# DIO-SMA16-MEZZ.net
KiCad netlist of a schematic drawn in Altium Designer
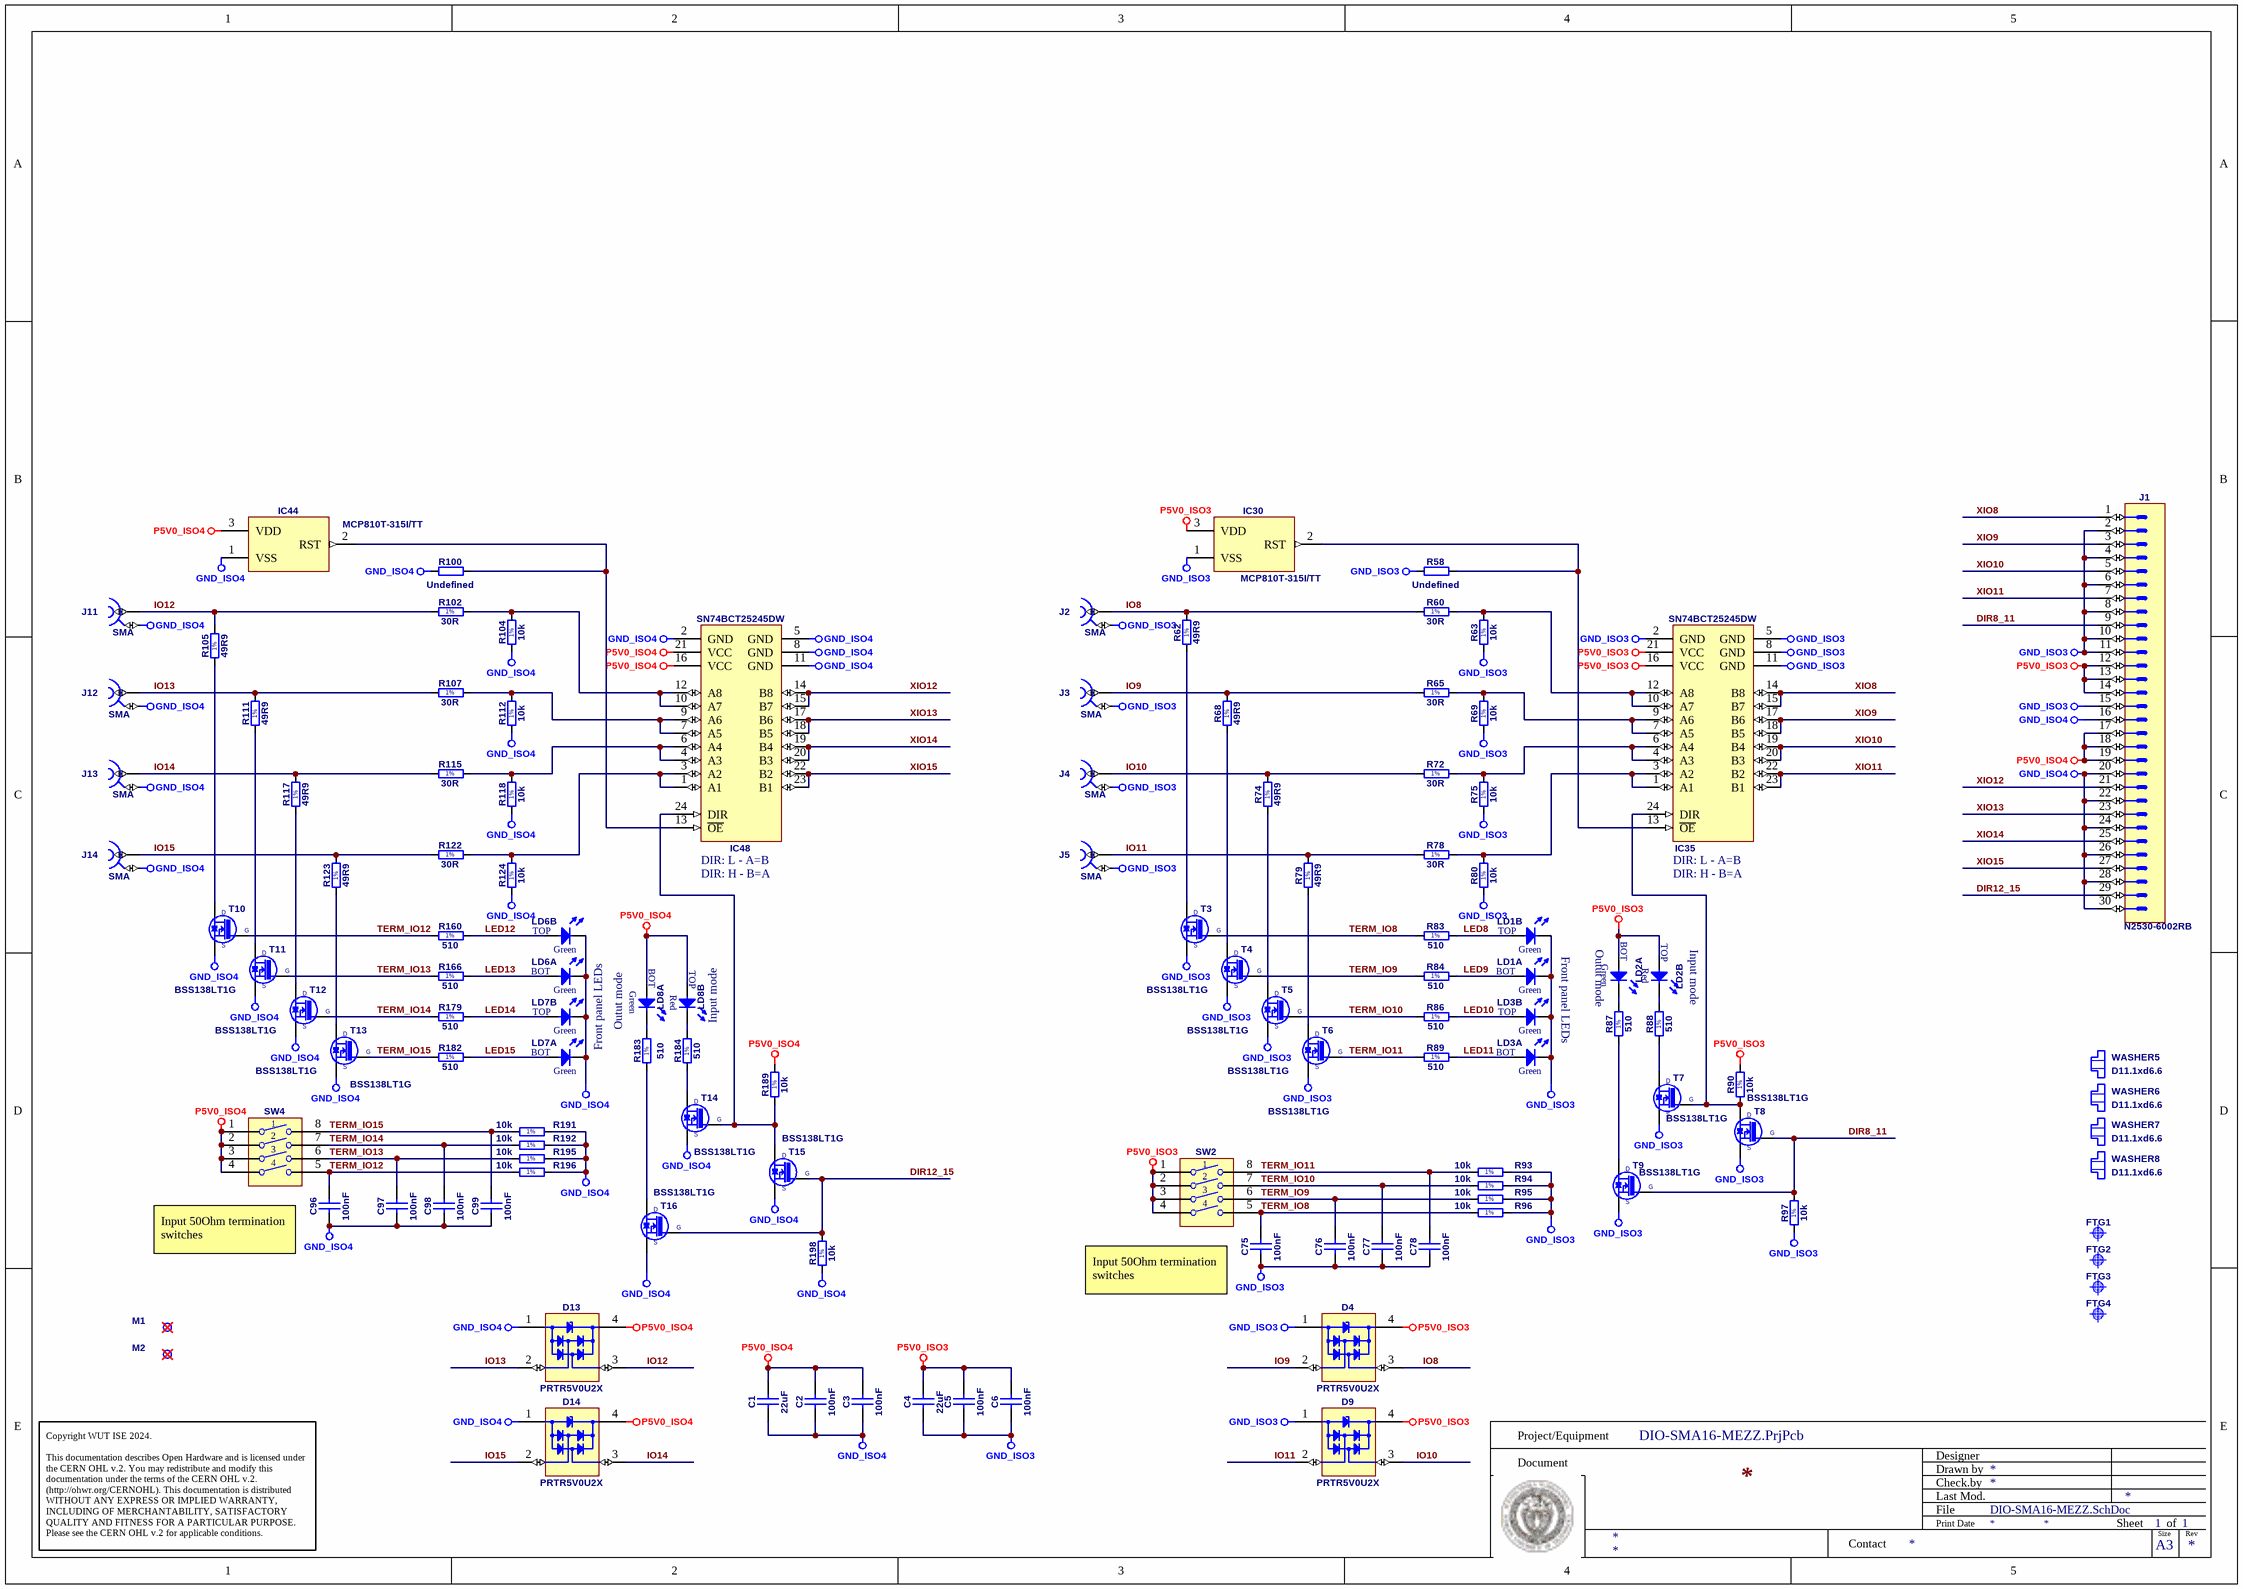
[diagram p0: DIO-SMA16-MEZZ.SchDoc]

(export (version "E")
  (design (tool "Eeschema 10.0.6"))
  (components
    (comp (ref "C1")
      (value "22uF")
      (footprint "CAPC2012X135N")
      (description "Non-polarised capacitor")
      (fields
        (field (name "PART NUMBER") "CC0805_22UF_16V_10%_X5R")
        (field (name "VOLTAGE") "16V")
        (field (name "AUTHOR") "CERN DEM JLC")
      )
      (libsource (lib "Capacitors") (part "Capacitor - non polarized"))
    )
    (comp (ref "C2")
      (value "100nF")
      (footprint "CAPC1005X55N")
      (description "Non-polarised capacitor")
      (fields
        (field (name "PART NUMBER") "CC0402_100NF_16V_10%_X5R")
        (field (name "VOLTAGE") "16V")
        (field (name "AUTHOR") "CERN DEM JLC")
      )
      (libsource (lib "Capacitors") (part "Capacitor - non polarized"))
    )
    (comp (ref "C3")
      (value "100nF")
      (footprint "CAPC1005X55N")
      (description "Non-polarised capacitor")
      (fields
        (field (name "PART NUMBER") "CC0402_100NF_16V_10%_X5R")
        (field (name "VOLTAGE") "16V")
        (field (name "AUTHOR") "CERN DEM JLC")
      )
      (libsource (lib "Capacitors") (part "Capacitor - non polarized"))
    )
    (comp (ref "C4")
      (value "22uF")
      (footprint "CAPC2012X135N")
      (description "Non-polarised capacitor")
      (fields
        (field (name "PART NUMBER") "CC0805_22UF_16V_10%_X5R")
        (field (name "VOLTAGE") "16V")
        (field (name "AUTHOR") "CERN DEM JLC")
      )
      (libsource (lib "Capacitors") (part "Capacitor - non polarized"))
    )
    (comp (ref "C5")
      (value "100nF")
      (footprint "CAPC1005X55N")
      (description "Non-polarised capacitor")
      (fields
        (field (name "PART NUMBER") "CC0402_100NF_16V_10%_X5R")
        (field (name "VOLTAGE") "16V")
        (field (name "AUTHOR") "CERN DEM JLC")
      )
      (libsource (lib "Capacitors") (part "Capacitor - non polarized"))
    )
    (comp (ref "C6")
      (value "100nF")
      (footprint "CAPC1005X55N")
      (description "Non-polarised capacitor")
      (fields
        (field (name "PART NUMBER") "CC0402_100NF_16V_10%_X5R")
        (field (name "VOLTAGE") "16V")
        (field (name "AUTHOR") "CERN DEM JLC")
      )
      (libsource (lib "Capacitors") (part "Capacitor - non polarized"))
    )
    (comp (ref "C75")
      (value "100nF")
      (footprint "CAPC1005X55N")
      (description "Non-polarised capacitor")
      (fields
        (field (name "PART NUMBER") "CC0402_100NF_16V_10%_X5R")
        (field (name "VOLTAGE") "16V")
        (field (name "AUTHOR") "CERN DEM JLC")
      )
      (libsource (lib "Capacitors") (part "Capacitor - non polarized"))
    )
    (comp (ref "C76")
      (value "100nF")
      (footprint "CAPC1005X55N")
      (description "Non-polarised capacitor")
      (fields
        (field (name "PART NUMBER") "CC0402_100NF_16V_10%_X5R")
        (field (name "VOLTAGE") "16V")
        (field (name "AUTHOR") "CERN DEM JLC")
      )
      (libsource (lib "Capacitors") (part "Capacitor - non polarized"))
    )
    (comp (ref "C77")
      (value "100nF")
      (footprint "CAPC1005X55N")
      (description "Non-polarised capacitor")
      (fields
        (field (name "PART NUMBER") "CC0402_100NF_16V_10%_X5R")
        (field (name "VOLTAGE") "16V")
        (field (name "AUTHOR") "CERN DEM JLC")
      )
      (libsource (lib "Capacitors") (part "Capacitor - non polarized"))
    )
    (comp (ref "C78")
      (value "100nF")
      (footprint "CAPC1005X55N")
      (description "Non-polarised capacitor")
      (fields
        (field (name "PART NUMBER") "CC0402_100NF_16V_10%_X5R")
        (field (name "VOLTAGE") "16V")
        (field (name "AUTHOR") "CERN DEM JLC")
      )
      (libsource (lib "Capacitors") (part "Capacitor - non polarized"))
    )
    (comp (ref "C96")
      (value "100nF")
      (footprint "CAPC1005X55N")
      (description "Non-polarised capacitor")
      (fields
        (field (name "PART NUMBER") "CC0402_100NF_16V_10%_X5R")
        (field (name "VOLTAGE") "16V")
        (field (name "AUTHOR") "CERN DEM JLC")
      )
      (libsource (lib "Capacitors") (part "Capacitor - non polarized"))
    )
    (comp (ref "C97")
      (value "100nF")
      (footprint "CAPC1005X55N")
      (description "Non-polarised capacitor")
      (fields
        (field (name "PART NUMBER") "CC0402_100NF_16V_10%_X5R")
        (field (name "VOLTAGE") "16V")
        (field (name "AUTHOR") "CERN DEM JLC")
      )
      (libsource (lib "Capacitors") (part "Capacitor - non polarized"))
    )
    (comp (ref "C98")
      (value "100nF")
      (footprint "CAPC1005X55N")
      (description "Non-polarised capacitor")
      (fields
        (field (name "PART NUMBER") "CC0402_100NF_16V_10%_X5R")
        (field (name "VOLTAGE") "16V")
        (field (name "AUTHOR") "CERN DEM JLC")
      )
      (libsource (lib "Capacitors") (part "Capacitor - non polarized"))
    )
    (comp (ref "C99")
      (value "100nF")
      (footprint "CAPC1005X55N")
      (description "Non-polarised capacitor")
      (fields
        (field (name "PART NUMBER") "CC0402_100NF_16V_10%_X5R")
        (field (name "VOLTAGE") "16V")
        (field (name "AUTHOR") "CERN DEM JLC")
      )
      (libsource (lib "Capacitors") (part "Capacitor - non polarized"))
    )
    (comp (ref "D4")
      (value "PRTR5V0U2X")
      (footprint "SOT190P230X110-4N")
      (description "Ultra Low Capacitance Double Rail-to-Rail ESD Protection Diode")
      (fields
        (field (name "VOLTAGE") "5.5V")
        (field (name "MANUFACTURER") "NXP SEMICONDUCTORS")
        (field (name "AUTHOR") "CERN DEM JLC")
      )
      (libsource (lib "ICs And Semiconductors") (part "PRTR5V0U2X"))
    )
    (comp (ref "D9")
      (value "PRTR5V0U2X")
      (footprint "SOT190P230X110-4N")
      (description "Ultra Low Capacitance Double Rail-to-Rail ESD Protection Diode")
      (fields
        (field (name "VOLTAGE") "5.5V")
        (field (name "MANUFACTURER") "NXP SEMICONDUCTORS")
        (field (name "AUTHOR") "CERN DEM JLC")
      )
      (libsource (lib "ICs And Semiconductors") (part "PRTR5V0U2X"))
    )
    (comp (ref "D13")
      (value "PRTR5V0U2X")
      (footprint "SOT190P230X110-4N")
      (description "Ultra Low Capacitance Double Rail-to-Rail ESD Protection Diode")
      (fields
        (field (name "VOLTAGE") "5.5V")
        (field (name "MANUFACTURER") "NXP SEMICONDUCTORS")
        (field (name "AUTHOR") "CERN DEM JLC")
      )
      (libsource (lib "ICs And Semiconductors") (part "PRTR5V0U2X"))
    )
    (comp (ref "D14")
      (value "PRTR5V0U2X")
      (footprint "SOT190P230X110-4N")
      (description "Ultra Low Capacitance Double Rail-to-Rail ESD Protection Diode")
      (fields
        (field (name "VOLTAGE") "5.5V")
        (field (name "MANUFACTURER") "NXP SEMICONDUCTORS")
        (field (name "AUTHOR") "CERN DEM JLC")
      )
      (libsource (lib "ICs And Semiconductors") (part "PRTR5V0U2X"))
    )
    (comp (ref "FTG1")
      (value "Use only in PCB")
      (footprint "FIDUCIAL_TOP_C100-200")
      (description "Fiducial Target")
      (fields (field (name "PART NUMBER") "FIDUCIAL_TARGET_C100-200") (field (name "AUTHOR") "CERN DEM JLC"))
      (libsource (lib "Eletro-mechanical") (part "Fiducial Target"))
    )
    (comp (ref "FTG2")
      (value "Use only in PCB")
      (footprint "FIDUCIAL_TOP_S100-200")
      (description "Fiducial Target")
      (fields (field (name "PART NUMBER") "FIDUCIAL_TARGET_S100-200") (field (name "AUTHOR") "CERN DEM JLC"))
      (libsource (lib "Eletro-mechanical") (part "Fiducial Target"))
    )
    (comp (ref "FTG3")
      (value "Use only in PCB")
      (footprint "FIDUCIAL_TOP_S100-200")
      (description "Fiducial Target")
      (fields (field (name "PART NUMBER") "FIDUCIAL_TARGET_S100-200") (field (name "AUTHOR") "CERN DEM JLC"))
      (libsource (lib "Eletro-mechanical") (part "Fiducial Target"))
    )
    (comp (ref "FTG4")
      (value "Use only in PCB")
      (footprint "FIDUCIAL_TOP_S100-200")
      (description "Fiducial Target")
      (fields (field (name "PART NUMBER") "FIDUCIAL_TARGET_S100-200") (field (name "AUTHOR") "CERN DEM JLC"))
      (libsource (lib "Eletro-mechanical") (part "Fiducial Target"))
    )
    (comp (ref "IC30")
      (value "MCP810T-315I/TT")
      (footprint "SOT95P237X112-3N")
      (description "3.075V Microcontroller Supervisory Circuit With Push-Pull Output")
      (fields (field (name "MANUFACTURER") "MICROCHIP TECHNOLOGY") (field (name "AUTHOR") "GK"))
      (libsource (lib "LIBRARY_SCH") (part "VMON_MCP810"))
    )
    (comp (ref "IC35")
      (value "SN74BCT25245DW")
      (footprint "SOIC127P1030X265-24N")
      (description "25 Ohms Octal Bus Transceiver With 3-State Outputs")
      (fields (field (name "MANUFACTURER") "TEXAS INSTRUMENTS") (field (name "AUTHOR") "CERN DEM JLC"))
      (libsource (lib "ICs And Semiconductors") (part "7425245"))
    )
    (comp (ref "IC44")
      (value "MCP810T-315I/TT")
      (footprint "SOT95P237X112-3N")
      (description "3.075V Microcontroller Supervisory Circuit With Push-Pull Output")
      (fields (field (name "MANUFACTURER") "MICROCHIP TECHNOLOGY") (field (name "AUTHOR") "GK"))
      (libsource (lib "LIBRARY_SCH") (part "VMON_MCP810"))
    )
    (comp (ref "IC48")
      (value "SN74BCT25245DW")
      (footprint "SOIC127P1030X265-24N")
      (description "25 Ohms Octal Bus Transceiver With 3-State Outputs")
      (fields (field (name "MANUFACTURER") "TEXAS INSTRUMENTS") (field (name "AUTHOR") "CERN DEM JLC"))
      (libsource (lib "ICs And Semiconductors") (part "7425245"))
    )
    (comp (ref "J1")
      (value "~")
      (footprint "3M_N2530-6002RB")
      (description "Connector 30 Male")
      (fields
        (field (name "PART NUMBER") "3M_N2530-6002RB")
        (field (name "MANUFACTURER") "3M")
        (field (name "MANUFACTURER PART NUMBER") "N2530-6002RB")
        (field (name "AUTHOR") "CERN DEM JLC")
      )
      (libsource (lib "Connectors") (part "Connector 30 Male"))
    )
    (comp (ref "J2")
      (value "SMA")
      (footprint "DELOCK_65848")
      (description "50 Ohm Through Hole SMA Right Angle PCB Jack")
      (fields
        (field (name "PART NUMBER") "DELOCK_65848")
        (field (name "MANUFACTURER") "DELOCK")
        (field (name "AUTHOR") "GK")
      )
      (libsource (lib "Connectors") (part "CON_SMA_DELOCK_65848"))
    )
    (comp (ref "J3")
      (value "SMA")
      (footprint "MOLEX_73251-2121")
      (fields
        (field (name "PART NUMBER") "MOLEX_73251-2121")
        (field (name "MANUFACTURER") "MOLEX")
        (field (name "MANUFACTURER PART NUMBER") "73251-2121")
        (field (name "AUTHOR") "CERN DEM JLC")
      )
      (libsource (lib "Connectors") (part "Coax_1Female_1Shield"))
    )
    (comp (ref "J4")
      (value "SMA")
      (footprint "DELOCK_65848")
      (description "50 Ohm Through Hole SMA Right Angle PCB Jack")
      (fields
        (field (name "PART NUMBER") "DELOCK_65848")
        (field (name "MANUFACTURER") "DELOCK")
        (field (name "AUTHOR") "GK")
      )
      (libsource (lib "Connectors") (part "CON_SMA_DELOCK_65848"))
    )
    (comp (ref "J5")
      (value "SMA")
      (footprint "MOLEX_73251-2121")
      (fields
        (field (name "PART NUMBER") "MOLEX_73251-2121")
        (field (name "MANUFACTURER") "MOLEX")
        (field (name "MANUFACTURER PART NUMBER") "73251-2121")
        (field (name "AUTHOR") "CERN DEM JLC")
      )
      (libsource (lib "Connectors") (part "Coax_1Female_1Shield"))
    )
    (comp (ref "J11")
      (value "SMA")
      (footprint "DELOCK_65848")
      (description "50 Ohm Through Hole SMA Right Angle PCB Jack")
      (fields
        (field (name "PART NUMBER") "DELOCK_65848")
        (field (name "MANUFACTURER") "DELOCK")
        (field (name "AUTHOR") "GK")
      )
      (libsource (lib "Connectors") (part "CON_SMA_DELOCK_65848"))
    )
    (comp (ref "J12")
      (value "SMA")
      (footprint "MOLEX_73251-2121")
      (fields
        (field (name "PART NUMBER") "MOLEX_73251-2121")
        (field (name "MANUFACTURER") "MOLEX")
        (field (name "MANUFACTURER PART NUMBER") "73251-2121")
        (field (name "AUTHOR") "CERN DEM JLC")
      )
      (libsource (lib "Connectors") (part "Coax_1Female_1Shield"))
    )
    (comp (ref "J13")
      (value "SMA")
      (footprint "DELOCK_65848")
      (description "50 Ohm Through Hole SMA Right Angle PCB Jack")
      (fields
        (field (name "PART NUMBER") "DELOCK_65848")
        (field (name "MANUFACTURER") "DELOCK")
        (field (name "AUTHOR") "GK")
      )
      (libsource (lib "Connectors") (part "CON_SMA_DELOCK_65848"))
    )
    (comp (ref "J14")
      (value "SMA")
      (footprint "MOLEX_73251-2121")
      (fields
        (field (name "PART NUMBER") "MOLEX_73251-2121")
        (field (name "MANUFACTURER") "MOLEX")
        (field (name "MANUFACTURER PART NUMBER") "73251-2121")
        (field (name "AUTHOR") "CERN DEM JLC")
      )
      (libsource (lib "Connectors") (part "Coax_1Female_1Shield"))
    )
    (comp (ref "LD1")
      (value "Green/Green")
      (footprint "LED_DIALIGHT_571-0122F")
      (description "LED x2 Green 1C2A-BOT_3C4A-TOP")
      (fields
        (field (name "PART NUMBER") "LED_DIALIGHT_571-0122F")
        (field (name "MANUFACTURER") "DIALIGHT")
        (field (name "AUTHOR") "CERN DEM JLC")
      )
      (libsource (lib "ICs And Semiconductors") (part "LED x2 Green 1C2A-BOT_3C4A-TOP"))
    )
    (comp (ref "LD2")
      (value "Red/Green")
      (footprint "LED_DIALIGHT_571-0112F")
      (description "2x LED  Botom Green, Top Red")
      (fields
        (field (name "PART NUMBER") "LED_DIALIGHT_571-0112F")
        (field (name "MANUFACTURER") "DIALIGHT")
        (field (name "AUTHOR") "CERN DEM JLC")
      )
      (libsource (lib "ICs And Semiconductors") (part "LED x2 G-1C2A-BOT_R-3C4A-TOP"))
    )
    (comp (ref "LD3")
      (value "Green/Green")
      (footprint "LED_DIALIGHT_571-0122F")
      (description "LED x2 Green 1C2A-BOT_3C4A-TOP")
      (fields
        (field (name "PART NUMBER") "LED_DIALIGHT_571-0122F")
        (field (name "MANUFACTURER") "DIALIGHT")
        (field (name "AUTHOR") "CERN DEM JLC")
      )
      (libsource (lib "ICs And Semiconductors") (part "LED x2 Green 1C2A-BOT_3C4A-TOP"))
    )
    (comp (ref "LD6")
      (value "Green/Green")
      (footprint "LED_DIALIGHT_571-0122F")
      (description "LED x2 Green 1C2A-BOT_3C4A-TOP")
      (fields
        (field (name "PART NUMBER") "LED_DIALIGHT_571-0122F")
        (field (name "MANUFACTURER") "DIALIGHT")
        (field (name "AUTHOR") "CERN DEM JLC")
      )
      (libsource (lib "ICs And Semiconductors") (part "LED x2 Green 1C2A-BOT_3C4A-TOP"))
    )
    (comp (ref "LD7")
      (value "Green/Green")
      (footprint "LED_DIALIGHT_571-0122F")
      (description "LED x2 Green 1C2A-BOT_3C4A-TOP")
      (fields
        (field (name "PART NUMBER") "LED_DIALIGHT_571-0122F")
        (field (name "MANUFACTURER") "DIALIGHT")
        (field (name "AUTHOR") "CERN DEM JLC")
      )
      (libsource (lib "ICs And Semiconductors") (part "LED x2 Green 1C2A-BOT_3C4A-TOP"))
    )
    (comp (ref "LD8")
      (value "Red/Green")
      (footprint "LED_DIALIGHT_571-0112F")
      (description "2x LED  Botom Green, Top Red")
      (fields
        (field (name "PART NUMBER") "LED_DIALIGHT_571-0112F")
        (field (name "MANUFACTURER") "DIALIGHT")
        (field (name "AUTHOR") "CERN DEM JLC")
      )
      (libsource (lib "ICs And Semiconductors") (part "LED x2 G-1C2A-BOT_R-3C4A-TOP"))
    )
    (comp (ref "M1")
      (value "Plated Hole")
      (footprint "MTG300_600")
      (description "Single Terminal Socket")
      (fields (field (name "PART NUMBER") "PLATED_HOLE3.0_PAD6.0") (field (name "AUTHOR") "CERN DEM JLC"))
      (libsource (lib "Eletro-mechanical") (part "Single Terminal Socket"))
    )
    (comp (ref "M2")
      (value "Plated Hole")
      (footprint "MTG300_600")
      (description "Single Terminal Socket")
      (fields (field (name "PART NUMBER") "PLATED_HOLE3.0_PAD6.0") (field (name "AUTHOR") "CERN DEM JLC"))
      (libsource (lib "Eletro-mechanical") (part "Single Terminal Socket"))
    )
    (comp (ref "R58")
      (value "Undefined")
      (footprint "RESC1005X40N")
      (description "Resistor")
      (fields (field (name "PART NUMBER") "R0402_NO-VALUE") (field (name "AUTHOR") "CERN DEM JLC"))
      (libsource (lib "Resistors") (part "Resistor"))
    )
    (comp (ref "R60")
      (value "30R")
      (footprint "RESC3225X70N")
      (description "Resistor - 5%")
      (fields
        (field (name "PART NUMBER") "R1210_30R_5%_0.5W_200ppm")
        (field (name "POWER") "0.5W")
        (field (name "AUTHOR") "CERN DEM JMW")
      )
      (libsource (lib "LIBRARY_SCH") (part "R1210_30R_5%_0.5W_200PPM"))
    )
    (comp (ref "R62")
      (value "49R9")
      (footprint "RESC3225X70N")
      (description "Resistor - 1%")
      (fields
        (field (name "PART NUMBER") "R1210_49R9_1%_0.5W_100PPM_VISHAY_CRCW")
        (field (name "POWER") "0.5W")
        (field (name "AUTHOR") "CERN DEM JMW")
      )
      (libsource (lib "Resistors") (part "Resistor - 1%"))
    )
    (comp (ref "R63")
      (value "10k")
      (footprint "RESC1005X40N")
      (description "Resistor - 1%")
      (fields
        (field (name "PART NUMBER") "R0402_10K_1%_0.0625W_100PPM")
        (field (name "POWER") "0.0625W")
        (field (name "AUTHOR") "CERN DEM JLC")
      )
      (libsource (lib "Resistors") (part "Resistor - 1%"))
    )
    (comp (ref "R65")
      (value "30R")
      (footprint "RESC3225X70N")
      (description "Resistor - 5%")
      (fields
        (field (name "PART NUMBER") "R1210_30R_5%_0.5W_200ppm")
        (field (name "POWER") "0.5W")
        (field (name "AUTHOR") "CERN DEM JMW")
      )
      (libsource (lib "LIBRARY_SCH") (part "R1210_30R_5%_0.5W_200PPM"))
    )
    (comp (ref "R68")
      (value "49R9")
      (footprint "RESC3225X70N")
      (description "Resistor - 1%")
      (fields
        (field (name "PART NUMBER") "R1210_49R9_1%_0.5W_100PPM_VISHAY_CRCW")
        (field (name "POWER") "0.5W")
        (field (name "AUTHOR") "CERN DEM JMW")
      )
      (libsource (lib "Resistors") (part "Resistor - 1%"))
    )
    (comp (ref "R69")
      (value "10k")
      (footprint "RESC1005X40N")
      (description "Resistor - 1%")
      (fields
        (field (name "PART NUMBER") "R0402_10K_1%_0.0625W_100PPM")
        (field (name "POWER") "0.0625W")
        (field (name "AUTHOR") "CERN DEM JLC")
      )
      (libsource (lib "Resistors") (part "Resistor - 1%"))
    )
    (comp (ref "R72")
      (value "30R")
      (footprint "RESC3225X70N")
      (description "Resistor - 5%")
      (fields
        (field (name "PART NUMBER") "R1210_30R_5%_0.5W_200ppm")
        (field (name "POWER") "0.5W")
        (field (name "AUTHOR") "CERN DEM JMW")
      )
      (libsource (lib "LIBRARY_SCH") (part "R1210_30R_5%_0.5W_200PPM"))
    )
    (comp (ref "R74")
      (value "49R9")
      (footprint "RESC3225X70N")
      (description "Resistor - 1%")
      (fields
        (field (name "PART NUMBER") "R1210_49R9_1%_0.5W_100PPM_VISHAY_CRCW")
        (field (name "POWER") "0.5W")
        (field (name "AUTHOR") "CERN DEM JMW")
      )
      (libsource (lib "Resistors") (part "Resistor - 1%"))
    )
    (comp (ref "R75")
      (value "10k")
      (footprint "RESC1005X40N")
      (description "Resistor - 1%")
      (fields
        (field (name "PART NUMBER") "R0402_10K_1%_0.0625W_100PPM")
        (field (name "POWER") "0.0625W")
        (field (name "AUTHOR") "CERN DEM JLC")
      )
      (libsource (lib "Resistors") (part "Resistor - 1%"))
    )
    (comp (ref "R78")
      (value "30R")
      (footprint "RESC3225X70N")
      (description "Resistor - 5%")
      (fields
        (field (name "PART NUMBER") "R1210_30R_5%_0.5W_200ppm")
        (field (name "POWER") "0.5W")
        (field (name "AUTHOR") "CERN DEM JMW")
      )
      (libsource (lib "LIBRARY_SCH") (part "R1210_30R_5%_0.5W_200PPM"))
    )
    (comp (ref "R79")
      (value "49R9")
      (footprint "RESC3225X70N")
      (description "Resistor - 1%")
      (fields
        (field (name "PART NUMBER") "R1210_49R9_1%_0.5W_100PPM_VISHAY_CRCW")
        (field (name "POWER") "0.5W")
        (field (name "AUTHOR") "CERN DEM JMW")
      )
      (libsource (lib "Resistors") (part "Resistor - 1%"))
    )
    (comp (ref "R80")
      (value "10k")
      (footprint "RESC1005X40N")
      (description "Resistor - 1%")
      (fields
        (field (name "PART NUMBER") "R0402_10K_1%_0.0625W_100PPM")
        (field (name "POWER") "0.0625W")
        (field (name "AUTHOR") "CERN DEM JLC")
      )
      (libsource (lib "Resistors") (part "Resistor - 1%"))
    )
    (comp (ref "R83")
      (value "510")
      (footprint "RESC1005X40N")
      (description "Resistor - 1%")
      (fields
        (field (name "PART NUMBER") "R0402_510R_1%_0.0625W_100PPM")
        (field (name "POWER") "0.0625W")
        (field (name "AUTHOR") "CERN DEM JLC")
      )
      (libsource (lib "Resistors") (part "Resistor - 1%"))
    )
    (comp (ref "R84")
      (value "510")
      (footprint "RESC1005X40N")
      (description "Resistor - 1%")
      (fields
        (field (name "PART NUMBER") "R0402_510R_1%_0.0625W_100PPM")
        (field (name "POWER") "0.0625W")
        (field (name "AUTHOR") "CERN DEM JLC")
      )
      (libsource (lib "Resistors") (part "Resistor - 1%"))
    )
    (comp (ref "R86")
      (value "510")
      (footprint "RESC1005X40N")
      (description "Resistor - 1%")
      (fields
        (field (name "PART NUMBER") "R0402_510R_1%_0.0625W_100PPM")
        (field (name "POWER") "0.0625W")
        (field (name "AUTHOR") "CERN DEM JLC")
      )
      (libsource (lib "Resistors") (part "Resistor - 1%"))
    )
    (comp (ref "R87")
      (value "510")
      (footprint "RESC1005X40N")
      (description "Resistor - 1%")
      (fields
        (field (name "PART NUMBER") "R0402_510R_1%_0.0625W_100PPM")
        (field (name "POWER") "0.0625W")
        (field (name "AUTHOR") "CERN DEM JLC")
      )
      (libsource (lib "Resistors") (part "Resistor - 1%"))
    )
    (comp (ref "R88")
      (value "510")
      (footprint "RESC1005X40N")
      (description "Resistor - 1%")
      (fields
        (field (name "PART NUMBER") "R0402_510R_1%_0.0625W_100PPM")
        (field (name "POWER") "0.0625W")
        (field (name "AUTHOR") "CERN DEM JLC")
      )
      (libsource (lib "Resistors") (part "Resistor - 1%"))
    )
    (comp (ref "R89")
      (value "510")
      (footprint "RESC1005X40N")
      (description "Resistor - 1%")
      (fields
        (field (name "PART NUMBER") "R0402_510R_1%_0.0625W_100PPM")
        (field (name "POWER") "0.0625W")
        (field (name "AUTHOR") "CERN DEM JLC")
      )
      (libsource (lib "Resistors") (part "Resistor - 1%"))
    )
    (comp (ref "R90")
      (value "10k")
      (footprint "RESC1005X40N")
      (description "Resistor - 1%")
      (fields
        (field (name "PART NUMBER") "R0402_10K_1%_0.0625W_100PPM")
        (field (name "POWER") "0.0625W")
        (field (name "AUTHOR") "CERN DEM JLC")
      )
      (libsource (lib "Resistors") (part "Resistor - 1%"))
    )
    (comp (ref "R93")
      (value "10k")
      (footprint "RESC1005X40N")
      (description "Resistor - 1%")
      (fields
        (field (name "PART NUMBER") "R0402_10K_1%_0.0625W_100PPM")
        (field (name "POWER") "0.0625W")
        (field (name "AUTHOR") "CERN DEM JLC")
      )
      (libsource (lib "Resistors") (part "Resistor - 1%"))
    )
    (comp (ref "R94")
      (value "10k")
      (footprint "RESC1005X40N")
      (description "Resistor - 1%")
      (fields
        (field (name "PART NUMBER") "R0402_10K_1%_0.0625W_100PPM")
        (field (name "POWER") "0.0625W")
        (field (name "AUTHOR") "CERN DEM JLC")
      )
      (libsource (lib "Resistors") (part "Resistor - 1%"))
    )
    (comp (ref "R95")
      (value "10k")
      (footprint "RESC1005X40N")
      (description "Resistor - 1%")
      (fields
        (field (name "PART NUMBER") "R0402_10K_1%_0.0625W_100PPM")
        (field (name "POWER") "0.0625W")
        (field (name "AUTHOR") "CERN DEM JLC")
      )
      (libsource (lib "Resistors") (part "Resistor - 1%"))
    )
    (comp (ref "R96")
      (value "10k")
      (footprint "RESC1005X40N")
      (description "Resistor - 1%")
      (fields
        (field (name "PART NUMBER") "R0402_10K_1%_0.0625W_100PPM")
        (field (name "POWER") "0.0625W")
        (field (name "AUTHOR") "CERN DEM JLC")
      )
      (libsource (lib "Resistors") (part "Resistor - 1%"))
    )
    (comp (ref "R97")
      (value "10k")
      (footprint "RESC1005X40N")
      (description "Resistor - 1%")
      (fields
        (field (name "PART NUMBER") "R0402_10K_1%_0.0625W_100PPM")
        (field (name "POWER") "0.0625W")
        (field (name "AUTHOR") "CERN DEM JLC")
      )
      (libsource (lib "Resistors") (part "Resistor - 1%"))
    )
    (comp (ref "R100")
      (value "Undefined")
      (footprint "RESC1005X40N")
      (description "Resistor")
      (fields (field (name "PART NUMBER") "R0402_NO-VALUE") (field (name "AUTHOR") "CERN DEM JLC"))
      (libsource (lib "Resistors") (part "Resistor"))
    )
    (comp (ref "R102")
      (value "30R")
      (footprint "RESC3225X70N")
      (description "Resistor - 5%")
      (fields
        (field (name "PART NUMBER") "R1210_30R_5%_0.5W_200ppm")
        (field (name "POWER") "0.5W")
        (field (name "AUTHOR") "CERN DEM JMW")
      )
      (libsource (lib "LIBRARY_SCH") (part "R1210_30R_5%_0.5W_200PPM"))
    )
    (comp (ref "R104")
      (value "10k")
      (footprint "RESC1005X40N")
      (description "Resistor - 1%")
      (fields
        (field (name "PART NUMBER") "R0402_10K_1%_0.0625W_100PPM")
        (field (name "POWER") "0.0625W")
        (field (name "AUTHOR") "CERN DEM JLC")
      )
      (libsource (lib "Resistors") (part "Resistor - 1%"))
    )
    (comp (ref "R105")
      (value "49R9")
      (footprint "RESC3225X70N")
      (description "Resistor - 1%")
      (fields
        (field (name "PART NUMBER") "R1210_49R9_1%_0.5W_100PPM_VISHAY_CRCW")
        (field (name "POWER") "0.5W")
        (field (name "AUTHOR") "CERN DEM JMW")
      )
      (libsource (lib "Resistors") (part "Resistor - 1%"))
    )
    (comp (ref "R107")
      (value "30R")
      (footprint "RESC3225X70N")
      (description "Resistor - 5%")
      (fields
        (field (name "PART NUMBER") "R1210_30R_5%_0.5W_200ppm")
        (field (name "POWER") "0.5W")
        (field (name "AUTHOR") "CERN DEM JMW")
      )
      (libsource (lib "LIBRARY_SCH") (part "R1210_30R_5%_0.5W_200PPM"))
    )
    (comp (ref "R111")
      (value "49R9")
      (footprint "RESC3225X70N")
      (description "Resistor - 1%")
      (fields
        (field (name "PART NUMBER") "R1210_49R9_1%_0.5W_100PPM_VISHAY_CRCW")
        (field (name "POWER") "0.5W")
        (field (name "AUTHOR") "CERN DEM JMW")
      )
      (libsource (lib "Resistors") (part "Resistor - 1%"))
    )
    (comp (ref "R112")
      (value "10k")
      (footprint "RESC1005X40N")
      (description "Resistor - 1%")
      (fields
        (field (name "PART NUMBER") "R0402_10K_1%_0.0625W_100PPM")
        (field (name "POWER") "0.0625W")
        (field (name "AUTHOR") "CERN DEM JLC")
      )
      (libsource (lib "Resistors") (part "Resistor - 1%"))
    )
    (comp (ref "R115")
      (value "30R")
      (footprint "RESC3225X70N")
      (description "Resistor - 5%")
      (fields
        (field (name "PART NUMBER") "R1210_30R_5%_0.5W_200ppm")
        (field (name "POWER") "0.5W")
        (field (name "AUTHOR") "CERN DEM JMW")
      )
      (libsource (lib "LIBRARY_SCH") (part "R1210_30R_5%_0.5W_200PPM"))
    )
    (comp (ref "R117")
      (value "49R9")
      (footprint "RESC3225X70N")
      (description "Resistor - 1%")
      (fields
        (field (name "PART NUMBER") "R1210_49R9_1%_0.5W_100PPM_VISHAY_CRCW")
        (field (name "POWER") "0.5W")
        (field (name "AUTHOR") "CERN DEM JMW")
      )
      (libsource (lib "Resistors") (part "Resistor - 1%"))
    )
    (comp (ref "R118")
      (value "10k")
      (footprint "RESC1005X40N")
      (description "Resistor - 1%")
      (fields
        (field (name "PART NUMBER") "R0402_10K_1%_0.0625W_100PPM")
        (field (name "POWER") "0.0625W")
        (field (name "AUTHOR") "CERN DEM JLC")
      )
      (libsource (lib "Resistors") (part "Resistor - 1%"))
    )
    (comp (ref "R122")
      (value "30R")
      (footprint "RESC3225X70N")
      (description "Resistor - 5%")
      (fields
        (field (name "PART NUMBER") "R1210_30R_5%_0.5W_200ppm")
        (field (name "POWER") "0.5W")
        (field (name "AUTHOR") "CERN DEM JMW")
      )
      (libsource (lib "LIBRARY_SCH") (part "R1210_30R_5%_0.5W_200PPM"))
    )
    (comp (ref "R123")
      (value "49R9")
      (footprint "RESC3225X70N")
      (description "Resistor - 1%")
      (fields
        (field (name "PART NUMBER") "R1210_49R9_1%_0.5W_100PPM_VISHAY_CRCW")
        (field (name "POWER") "0.5W")
        (field (name "AUTHOR") "CERN DEM JMW")
      )
      (libsource (lib "Resistors") (part "Resistor - 1%"))
    )
    (comp (ref "R124")
      (value "10k")
      (footprint "RESC1005X40N")
      (description "Resistor - 1%")
      (fields
        (field (name "PART NUMBER") "R0402_10K_1%_0.0625W_100PPM")
        (field (name "POWER") "0.0625W")
        (field (name "AUTHOR") "CERN DEM JLC")
      )
      (libsource (lib "Resistors") (part "Resistor - 1%"))
    )
    (comp (ref "R160")
      (value "510")
      (footprint "RESC1005X40N")
      (description "Resistor - 1%")
      (fields
        (field (name "PART NUMBER") "R0402_510R_1%_0.0625W_100PPM")
        (field (name "POWER") "0.0625W")
        (field (name "AUTHOR") "CERN DEM JLC")
      )
      (libsource (lib "Resistors") (part "Resistor - 1%"))
    )
    (comp (ref "R166")
      (value "510")
      (footprint "RESC1005X40N")
      (description "Resistor - 1%")
      (fields
        (field (name "PART NUMBER") "R0402_510R_1%_0.0625W_100PPM")
        (field (name "POWER") "0.0625W")
        (field (name "AUTHOR") "CERN DEM JLC")
      )
      (libsource (lib "Resistors") (part "Resistor - 1%"))
    )
    (comp (ref "R179")
      (value "510")
      (footprint "RESC1005X40N")
      (description "Resistor - 1%")
      (fields
        (field (name "PART NUMBER") "R0402_510R_1%_0.0625W_100PPM")
        (field (name "POWER") "0.0625W")
        (field (name "AUTHOR") "CERN DEM JLC")
      )
      (libsource (lib "Resistors") (part "Resistor - 1%"))
    )
    (comp (ref "R182")
      (value "510")
      (footprint "RESC1005X40N")
      (description "Resistor - 1%")
      (fields
        (field (name "PART NUMBER") "R0402_510R_1%_0.0625W_100PPM")
        (field (name "POWER") "0.0625W")
        (field (name "AUTHOR") "CERN DEM JLC")
      )
      (libsource (lib "Resistors") (part "Resistor - 1%"))
    )
    (comp (ref "R183")
      (value "510")
      (footprint "RESC1005X40N")
      (description "Resistor - 1%")
      (fields
        (field (name "PART NUMBER") "R0402_510R_1%_0.0625W_100PPM")
        (field (name "POWER") "0.0625W")
        (field (name "AUTHOR") "CERN DEM JLC")
      )
      (libsource (lib "Resistors") (part "Resistor - 1%"))
    )
    (comp (ref "R184")
      (value "510")
      (footprint "RESC1005X40N")
      (description "Resistor - 1%")
      (fields
        (field (name "PART NUMBER") "R0402_510R_1%_0.0625W_100PPM")
        (field (name "POWER") "0.0625W")
        (field (name "AUTHOR") "CERN DEM JLC")
      )
      (libsource (lib "Resistors") (part "Resistor - 1%"))
    )
    (comp (ref "R189")
      (value "10k")
      (footprint "RESC1005X40N")
      (description "Resistor - 1%")
      (fields
        (field (name "PART NUMBER") "R0402_10K_1%_0.0625W_100PPM")
        (field (name "POWER") "0.0625W")
        (field (name "AUTHOR") "CERN DEM JLC")
      )
      (libsource (lib "Resistors") (part "Resistor - 1%"))
    )
    (comp (ref "R191")
      (value "10k")
      (footprint "RESC1005X40N")
      (description "Resistor - 1%")
      (fields
        (field (name "PART NUMBER") "R0402_10K_1%_0.0625W_100PPM")
        (field (name "POWER") "0.0625W")
        (field (name "AUTHOR") "CERN DEM JLC")
      )
      (libsource (lib "Resistors") (part "Resistor - 1%"))
    )
    (comp (ref "R192")
      (value "10k")
      (footprint "RESC1005X40N")
      (description "Resistor - 1%")
      (fields
        (field (name "PART NUMBER") "R0402_10K_1%_0.0625W_100PPM")
        (field (name "POWER") "0.0625W")
        (field (name "AUTHOR") "CERN DEM JLC")
      )
      (libsource (lib "Resistors") (part "Resistor - 1%"))
    )
    (comp (ref "R195")
      (value "10k")
      (footprint "RESC1005X40N")
      (description "Resistor - 1%")
      (fields
        (field (name "PART NUMBER") "R0402_10K_1%_0.0625W_100PPM")
        (field (name "POWER") "0.0625W")
        (field (name "AUTHOR") "CERN DEM JLC")
      )
      (libsource (lib "Resistors") (part "Resistor - 1%"))
    )
    (comp (ref "R196")
      (value "10k")
      (footprint "RESC1005X40N")
      (description "Resistor - 1%")
      (fields
        (field (name "PART NUMBER") "R0402_10K_1%_0.0625W_100PPM")
        (field (name "POWER") "0.0625W")
        (field (name "AUTHOR") "CERN DEM JLC")
      )
      (libsource (lib "Resistors") (part "Resistor - 1%"))
    )
    (comp (ref "R198")
      (value "10k")
      (footprint "RESC1005X40N")
      (description "Resistor - 1%")
      (fields
        (field (name "PART NUMBER") "R0402_10K_1%_0.0625W_100PPM")
        (field (name "POWER") "0.0625W")
        (field (name "AUTHOR") "CERN DEM JLC")
      )
      (libsource (lib "Resistors") (part "Resistor - 1%"))
    )
    (comp (ref "SW2")
      (value "Switch")
      (footprint "SW_OMRON_A6S-4102-H")
      (description "4 Ways SPST DIP Switch")
      (fields
        (field (name "PART NUMBER") "SW_OMRON_A6S-4102-H")
        (field (name "MANUFACTURER") "OMRON")
        (field (name "AUTHOR") "CERN DEM JMW")
      )
      (libsource (lib "Eletro-mechanical") (part "SW 4x SPST DIP Switch"))
    )
    (comp (ref "SW4")
      (value "Switch")
      (footprint "SW_OMRON_A6S-4102-H")
      (description "4 Ways SPST DIP Switch")
      (fields
        (field (name "PART NUMBER") "SW_OMRON_A6S-4102-H")
        (field (name "MANUFACTURER") "OMRON")
        (field (name "AUTHOR") "CERN DEM JMW")
      )
      (libsource (lib "Eletro-mechanical") (part "SW 4x SPST DIP Switch"))
    )
    (comp (ref "T3")
      (value "BSS138LT1G")
      (footprint "SOT95P240X110-3N")
      (description "N-CHANNEL MOSFET WITH DIODE")
      (fields (field (name "MANUFACTURER") "ON SEMICONDUCTOR") (field (name "AUTHOR") "CERN DEM JLC"))
      (libsource (lib "ICs And Semiconductors") (part "N-MOSFET-D 1G 2S 3D"))
    )
    (comp (ref "T4")
      (value "BSS138LT1G")
      (footprint "SOT95P240X110-3N")
      (description "N-CHANNEL MOSFET WITH DIODE")
      (fields (field (name "MANUFACTURER") "ON SEMICONDUCTOR") (field (name "AUTHOR") "CERN DEM JLC"))
      (libsource (lib "ICs And Semiconductors") (part "N-MOSFET-D 1G 2S 3D"))
    )
    (comp (ref "T5")
      (value "BSS138LT1G")
      (footprint "SOT95P240X110-3N")
      (description "N-CHANNEL MOSFET WITH DIODE")
      (fields (field (name "MANUFACTURER") "ON SEMICONDUCTOR") (field (name "AUTHOR") "CERN DEM JLC"))
      (libsource (lib "ICs And Semiconductors") (part "N-MOSFET-D 1G 2S 3D"))
    )
    (comp (ref "T6")
      (value "BSS138LT1G")
      (footprint "SOT95P240X110-3N")
      (description "N-CHANNEL MOSFET WITH DIODE")
      (fields (field (name "MANUFACTURER") "ON SEMICONDUCTOR") (field (name "AUTHOR") "CERN DEM JLC"))
      (libsource (lib "ICs And Semiconductors") (part "N-MOSFET-D 1G 2S 3D"))
    )
    (comp (ref "T7")
      (value "BSS138LT1G")
      (footprint "SOT95P240X110-3N")
      (description "N-CHANNEL MOSFET WITH DIODE")
      (fields (field (name "MANUFACTURER") "ON SEMICONDUCTOR") (field (name "AUTHOR") "CERN DEM JLC"))
      (libsource (lib "ICs And Semiconductors") (part "N-MOSFET-D 1G 2S 3D"))
    )
    (comp (ref "T8")
      (value "BSS138LT1G")
      (footprint "SOT95P240X110-3N")
      (description "N-CHANNEL MOSFET WITH DIODE")
      (fields (field (name "MANUFACTURER") "ON SEMICONDUCTOR") (field (name "AUTHOR") "CERN DEM JLC"))
      (libsource (lib "ICs And Semiconductors") (part "N-MOSFET-D 1G 2S 3D"))
    )
    (comp (ref "T9")
      (value "BSS138LT1G")
      (footprint "SOT95P240X110-3N")
      (description "N-CHANNEL MOSFET WITH DIODE")
      (fields (field (name "MANUFACTURER") "ON SEMICONDUCTOR") (field (name "AUTHOR") "CERN DEM JLC"))
      (libsource (lib "ICs And Semiconductors") (part "N-MOSFET-D 1G 2S 3D"))
    )
    (comp (ref "T10")
      (value "BSS138LT1G")
      (footprint "SOT95P240X110-3N")
      (description "N-CHANNEL MOSFET WITH DIODE")
      (fields (field (name "MANUFACTURER") "ON SEMICONDUCTOR") (field (name "AUTHOR") "CERN DEM JLC"))
      (libsource (lib "ICs And Semiconductors") (part "N-MOSFET-D 1G 2S 3D"))
    )
    (comp (ref "T11")
      (value "BSS138LT1G")
      (footprint "SOT95P240X110-3N")
      (description "N-CHANNEL MOSFET WITH DIODE")
      (fields (field (name "MANUFACTURER") "ON SEMICONDUCTOR") (field (name "AUTHOR") "CERN DEM JLC"))
      (libsource (lib "ICs And Semiconductors") (part "N-MOSFET-D 1G 2S 3D"))
    )
    (comp (ref "T12")
      (value "BSS138LT1G")
      (footprint "SOT95P240X110-3N")
      (description "N-CHANNEL MOSFET WITH DIODE")
      (fields (field (name "MANUFACTURER") "ON SEMICONDUCTOR") (field (name "AUTHOR") "CERN DEM JLC"))
      (libsource (lib "ICs And Semiconductors") (part "N-MOSFET-D 1G 2S 3D"))
    )
    (comp (ref "T13")
      (value "BSS138LT1G")
      (footprint "SOT95P240X110-3N")
      (description "N-CHANNEL MOSFET WITH DIODE")
      (fields (field (name "MANUFACTURER") "ON SEMICONDUCTOR") (field (name "AUTHOR") "CERN DEM JLC"))
      (libsource (lib "ICs And Semiconductors") (part "N-MOSFET-D 1G 2S 3D"))
    )
    (comp (ref "T14")
      (value "BSS138LT1G")
      (footprint "SOT95P240X110-3N")
      (description "N-CHANNEL MOSFET WITH DIODE")
      (fields (field (name "MANUFACTURER") "ON SEMICONDUCTOR") (field (name "AUTHOR") "CERN DEM JLC"))
      (libsource (lib "ICs And Semiconductors") (part "N-MOSFET-D 1G 2S 3D"))
    )
    (comp (ref "T15")
      (value "BSS138LT1G")
      (footprint "SOT95P240X110-3N")
      (description "N-CHANNEL MOSFET WITH DIODE")
      (fields (field (name "MANUFACTURER") "ON SEMICONDUCTOR") (field (name "AUTHOR") "CERN DEM JLC"))
      (libsource (lib "ICs And Semiconductors") (part "N-MOSFET-D 1G 2S 3D"))
    )
    (comp (ref "T16")
      (value "BSS138LT1G")
      (footprint "SOT95P240X110-3N")
      (description "N-CHANNEL MOSFET WITH DIODE")
      (fields (field (name "MANUFACTURER") "ON SEMICONDUCTOR") (field (name "AUTHOR") "CERN DEM JLC"))
      (libsource (lib "ICs And Semiconductors") (part "N-MOSFET-D 1G 2S 3D"))
    )
    (comp (ref "WASHER5")
      (value "D11.1xd6.6")
      (footprint "Keystone_7687")
      (description "SMA_Shoulder Washer")
      (fields (field (name "PART NUMBER") "Custom 3D") (field (name "AUTHOR") "GK"))
      (libsource (lib "LIBRARY_SCH") (part "Keystone_7687"))
    )
    (comp (ref "WASHER6")
      (value "D11.1xd6.6")
      (footprint "Keystone_7687")
      (description "SMA_Shoulder Washer")
      (fields (field (name "PART NUMBER") "Custom 3D") (field (name "AUTHOR") "GK"))
      (libsource (lib "LIBRARY_SCH") (part "Keystone_7687"))
    )
    (comp (ref "WASHER7")
      (value "D11.1xd6.6")
      (footprint "Keystone_7687")
      (description "SMA_Shoulder Washer")
      (fields (field (name "PART NUMBER") "Custom 3D") (field (name "AUTHOR") "GK"))
      (libsource (lib "LIBRARY_SCH") (part "Keystone_7687"))
    )
    (comp (ref "WASHER8")
      (value "D11.1xd6.6")
      (footprint "Keystone_7687")
      (description "SMA_Shoulder Washer")
      (fields (field (name "PART NUMBER") "Custom 3D") (field (name "AUTHOR") "GK"))
      (libsource (lib "LIBRARY_SCH") (part "Keystone_7687"))
    )
  )
  (nets
    (net (code "1") (name "/DIR8_11") (class "Default")
      (node (ref "J1") (pin "9") (pinfunction "9_9") (pintype "bidirectional"))
      (node (ref "R97") (pin "2") (pinfunction "2_2") (pintype "passive"))
      (node (ref "T8") (pin "1") (pinfunction "G_1") (pintype "passive"))
      (node (ref "T9") (pin "1") (pinfunction "G_1") (pintype "passive"))
    )
    (net (code "2") (name "/DIR12_15") (class "Default")
      (node (ref "J1") (pin "29") (pinfunction "29_29") (pintype "bidirectional"))
      (node (ref "R198") (pin "2") (pinfunction "2_2") (pintype "passive"))
      (node (ref "T15") (pin "1") (pinfunction "G_1") (pintype "passive"))
      (node (ref "T16") (pin "1") (pinfunction "G_1") (pintype "passive"))
    )
    (net (code "3") (name "/IO8") (class "Default")
      (node (ref "D4") (pin "3") (pinfunction "I/O2_3") (pintype "bidirectional"))
      (node (ref "J2") (pin "1") (pinfunction "1_1") (pintype "bidirectional"))
      (node (ref "R60") (pin "1") (pinfunction "1_1") (pintype "passive"))
      (node (ref "R62") (pin "2") (pinfunction "2_2") (pintype "passive"))
    )
    (net (code "4") (name "/IO9") (class "Default")
      (node (ref "D4") (pin "2") (pinfunction "I/O1_2") (pintype "bidirectional"))
      (node (ref "J3") (pin "1") (pinfunction "1_1") (pintype "bidirectional"))
      (node (ref "R65") (pin "1") (pinfunction "1_1") (pintype "passive"))
      (node (ref "R68") (pin "2") (pinfunction "2_2") (pintype "passive"))
    )
    (net (code "5") (name "/IO10") (class "Default")
      (node (ref "D9") (pin "3") (pinfunction "I/O2_3") (pintype "bidirectional"))
      (node (ref "J4") (pin "1") (pinfunction "1_1") (pintype "bidirectional"))
      (node (ref "R72") (pin "1") (pinfunction "1_1") (pintype "passive"))
      (node (ref "R74") (pin "2") (pinfunction "2_2") (pintype "passive"))
    )
    (net (code "6") (name "/IO11") (class "Default")
      (node (ref "D9") (pin "2") (pinfunction "I/O1_2") (pintype "bidirectional"))
      (node (ref "J5") (pin "1") (pinfunction "1_1") (pintype "bidirectional"))
      (node (ref "R78") (pin "1") (pinfunction "1_1") (pintype "passive"))
      (node (ref "R79") (pin "2") (pinfunction "2_2") (pintype "passive"))
    )
    (net (code "7") (name "/IO12") (class "Default")
      (node (ref "D13") (pin "3") (pinfunction "I/O2_3") (pintype "bidirectional"))
      (node (ref "J11") (pin "1") (pinfunction "1_1") (pintype "bidirectional"))
      (node (ref "R102") (pin "1") (pinfunction "1_1") (pintype "passive"))
      (node (ref "R105") (pin "2") (pinfunction "2_2") (pintype "passive"))
    )
    (net (code "8") (name "/IO13") (class "Default")
      (node (ref "D13") (pin "2") (pinfunction "I/O1_2") (pintype "bidirectional"))
      (node (ref "J12") (pin "1") (pinfunction "1_1") (pintype "bidirectional"))
      (node (ref "R107") (pin "1") (pinfunction "1_1") (pintype "passive"))
      (node (ref "R111") (pin "2") (pinfunction "2_2") (pintype "passive"))
    )
    (net (code "9") (name "/IO14") (class "Default")
      (node (ref "D14") (pin "3") (pinfunction "I/O2_3") (pintype "bidirectional"))
      (node (ref "J13") (pin "1") (pinfunction "1_1") (pintype "bidirectional"))
      (node (ref "R115") (pin "1") (pinfunction "1_1") (pintype "passive"))
      (node (ref "R117") (pin "2") (pinfunction "2_2") (pintype "passive"))
    )
    (net (code "10") (name "/IO15") (class "Default")
      (node (ref "D14") (pin "2") (pinfunction "I/O1_2") (pintype "bidirectional"))
      (node (ref "J14") (pin "1") (pinfunction "1_1") (pintype "bidirectional"))
      (node (ref "R122") (pin "1") (pinfunction "1_1") (pintype "passive"))
      (node (ref "R123") (pin "2") (pinfunction "2_2") (pintype "passive"))
    )
    (net (code "11") (name "/LED8") (class "Default")
      (node (ref "LD1") (pin "4") (pinfunction "A_4") (pintype "passive"))
      (node (ref "R83") (pin "2") (pinfunction "2_2") (pintype "passive"))
    )
    (net (code "12") (name "/LED9") (class "Default")
      (node (ref "LD1") (pin "2") (pinfunction "A_2") (pintype "passive"))
      (node (ref "R84") (pin "2") (pinfunction "2_2") (pintype "passive"))
    )
    (net (code "13") (name "/LED10") (class "Default")
      (node (ref "LD3") (pin "4") (pinfunction "A_4") (pintype "passive"))
      (node (ref "R86") (pin "2") (pinfunction "2_2") (pintype "passive"))
    )
    (net (code "14") (name "/LED11") (class "Default")
      (node (ref "LD3") (pin "2") (pinfunction "A_2") (pintype "passive"))
      (node (ref "R89") (pin "2") (pinfunction "2_2") (pintype "passive"))
    )
    (net (code "15") (name "/LED12") (class "Default")
      (node (ref "LD6") (pin "4") (pinfunction "A_4") (pintype "passive"))
      (node (ref "R160") (pin "2") (pinfunction "2_2") (pintype "passive"))
    )
    (net (code "16") (name "/LED13") (class "Default")
      (node (ref "LD6") (pin "2") (pinfunction "A_2") (pintype "passive"))
      (node (ref "R166") (pin "2") (pinfunction "2_2") (pintype "passive"))
    )
    (net (code "17") (name "/LED14") (class "Default")
      (node (ref "LD7") (pin "4") (pinfunction "A_4") (pintype "passive"))
      (node (ref "R179") (pin "2") (pinfunction "2_2") (pintype "passive"))
    )
    (net (code "18") (name "/LED15") (class "Default")
      (node (ref "LD7") (pin "2") (pinfunction "A_2") (pintype "passive"))
      (node (ref "R182") (pin "2") (pinfunction "2_2") (pintype "passive"))
    )
    (net (code "19") (name "/TERM_IO8") (class "Default")
      (node (ref "C75") (pin "2") (pinfunction "2_2") (pintype "passive"))
      (node (ref "R83") (pin "1") (pinfunction "1_1") (pintype "passive"))
      (node (ref "R96") (pin "1") (pinfunction "1_1") (pintype "passive"))
      (node (ref "SW2") (pin "5") (pinfunction "5_5") (pintype "passive"))
      (node (ref "T3") (pin "1") (pinfunction "G_1") (pintype "passive"))
    )
    (net (code "20") (name "/TERM_IO9") (class "Default")
      (node (ref "C76") (pin "2") (pinfunction "2_2") (pintype "passive"))
      (node (ref "R84") (pin "1") (pinfunction "1_1") (pintype "passive"))
      (node (ref "R95") (pin "1") (pinfunction "1_1") (pintype "passive"))
      (node (ref "SW2") (pin "6") (pinfunction "6_6") (pintype "passive"))
      (node (ref "T4") (pin "1") (pinfunction "G_1") (pintype "passive"))
    )
    (net (code "21") (name "/TERM_IO10") (class "Default")
      (node (ref "C77") (pin "2") (pinfunction "2_2") (pintype "passive"))
      (node (ref "R86") (pin "1") (pinfunction "1_1") (pintype "passive"))
      (node (ref "R94") (pin "1") (pinfunction "1_1") (pintype "passive"))
      (node (ref "SW2") (pin "7") (pinfunction "7_7") (pintype "passive"))
      (node (ref "T5") (pin "1") (pinfunction "G_1") (pintype "passive"))
    )
    (net (code "22") (name "/TERM_IO11") (class "Default")
      (node (ref "C78") (pin "2") (pinfunction "2_2") (pintype "passive"))
      (node (ref "R89") (pin "1") (pinfunction "1_1") (pintype "passive"))
      (node (ref "R93") (pin "1") (pinfunction "1_1") (pintype "passive"))
      (node (ref "SW2") (pin "8") (pinfunction "8_8") (pintype "passive"))
      (node (ref "T6") (pin "1") (pinfunction "G_1") (pintype "passive"))
    )
    (net (code "23") (name "/TERM_IO12") (class "Default")
      (node (ref "C96") (pin "2") (pinfunction "2_2") (pintype "passive"))
      (node (ref "R160") (pin "1") (pinfunction "1_1") (pintype "passive"))
      (node (ref "R196") (pin "1") (pinfunction "1_1") (pintype "passive"))
      (node (ref "SW4") (pin "5") (pinfunction "5_5") (pintype "passive"))
      (node (ref "T10") (pin "1") (pinfunction "G_1") (pintype "passive"))
    )
    (net (code "24") (name "/TERM_IO13") (class "Default")
      (node (ref "C97") (pin "2") (pinfunction "2_2") (pintype "passive"))
      (node (ref "R166") (pin "1") (pinfunction "1_1") (pintype "passive"))
      (node (ref "R195") (pin "1") (pinfunction "1_1") (pintype "passive"))
      (node (ref "SW4") (pin "6") (pinfunction "6_6") (pintype "passive"))
      (node (ref "T11") (pin "1") (pinfunction "G_1") (pintype "passive"))
    )
    (net (code "25") (name "/TERM_IO14") (class "Default")
      (node (ref "C98") (pin "2") (pinfunction "2_2") (pintype "passive"))
      (node (ref "R179") (pin "1") (pinfunction "1_1") (pintype "passive"))
      (node (ref "R192") (pin "1") (pinfunction "1_1") (pintype "passive"))
      (node (ref "SW4") (pin "7") (pinfunction "7_7") (pintype "passive"))
      (node (ref "T12") (pin "1") (pinfunction "G_1") (pintype "passive"))
    )
    (net (code "26") (name "/TERM_IO15") (class "Default")
      (node (ref "C99") (pin "2") (pinfunction "2_2") (pintype "passive"))
      (node (ref "R182") (pin "1") (pinfunction "1_1") (pintype "passive"))
      (node (ref "R191") (pin "1") (pinfunction "1_1") (pintype "passive"))
      (node (ref "SW4") (pin "8") (pinfunction "8_8") (pintype "passive"))
      (node (ref "T13") (pin "1") (pinfunction "G_1") (pintype "passive"))
    )
    (net (code "27") (name "/XIO8") (class "Default")
      (node (ref "IC35") (pin "14") (pinfunction "B8_14") (pintype "bidirectional"))
      (node (ref "IC35") (pin "15") (pinfunction "B7_15") (pintype "bidirectional"))
      (node (ref "J1") (pin "1") (pinfunction "1_1") (pintype "bidirectional"))
    )
    (net (code "28") (name "/XIO9") (class "Default")
      (node (ref "IC35") (pin "17") (pinfunction "B6_17") (pintype "bidirectional"))
      (node (ref "IC35") (pin "18") (pinfunction "B5_18") (pintype "bidirectional"))
      (node (ref "J1") (pin "3") (pinfunction "3_3") (pintype "bidirectional"))
    )
    (net (code "29") (name "/XIO10") (class "Default")
      (node (ref "IC35") (pin "19") (pinfunction "B4_19") (pintype "bidirectional"))
      (node (ref "IC35") (pin "20") (pinfunction "B3_20") (pintype "bidirectional"))
      (node (ref "J1") (pin "5") (pinfunction "5_5") (pintype "bidirectional"))
    )
    (net (code "30") (name "/XIO11") (class "Default")
      (node (ref "IC35") (pin "22") (pinfunction "B2_22") (pintype "bidirectional"))
      (node (ref "IC35") (pin "23") (pinfunction "B1_23") (pintype "bidirectional"))
      (node (ref "J1") (pin "7") (pinfunction "7_7") (pintype "bidirectional"))
    )
    (net (code "31") (name "/XIO12") (class "Default")
      (node (ref "IC48") (pin "14") (pinfunction "B8_14") (pintype "bidirectional"))
      (node (ref "IC48") (pin "15") (pinfunction "B7_15") (pintype "bidirectional"))
      (node (ref "J1") (pin "21") (pinfunction "21_21") (pintype "bidirectional"))
    )
    (net (code "32") (name "/XIO13") (class "Default")
      (node (ref "IC48") (pin "17") (pinfunction "B6_17") (pintype "bidirectional"))
      (node (ref "IC48") (pin "18") (pinfunction "B5_18") (pintype "bidirectional"))
      (node (ref "J1") (pin "23") (pinfunction "23_23") (pintype "bidirectional"))
    )
    (net (code "33") (name "/XIO14") (class "Default")
      (node (ref "IC48") (pin "19") (pinfunction "B4_19") (pintype "bidirectional"))
      (node (ref "IC48") (pin "20") (pinfunction "B3_20") (pintype "bidirectional"))
      (node (ref "J1") (pin "25") (pinfunction "25_25") (pintype "bidirectional"))
    )
    (net (code "34") (name "/XIO15") (class "Default")
      (node (ref "IC48") (pin "22") (pinfunction "B2_22") (pintype "bidirectional"))
      (node (ref "IC48") (pin "23") (pinfunction "B1_23") (pintype "bidirectional"))
      (node (ref "J1") (pin "27") (pinfunction "27_27") (pintype "bidirectional"))
    )
    (net (code "35") (name "GND_ISO3") (class "Default")
      (node (ref "C4") (pin "1") (pinfunction "1_1") (pintype "passive"))
      (node (ref "C5") (pin "1") (pinfunction "1_1") (pintype "passive"))
      (node (ref "C6") (pin "1") (pinfunction "1_1") (pintype "passive"))
      (node (ref "C75") (pin "1") (pinfunction "1_1") (pintype "passive"))
      (node (ref "C76") (pin "1") (pinfunction "1_1") (pintype "passive"))
      (node (ref "C77") (pin "1") (pinfunction "1_1") (pintype "passive"))
      (node (ref "C78") (pin "1") (pinfunction "1_1") (pintype "passive"))
      (node (ref "D4") (pin "1") (pinfunction "GND_1") (pintype "power_in"))
      (node (ref "D9") (pin "1") (pinfunction "GND_1") (pintype "power_in"))
      (node (ref "IC30") (pin "1") (pinfunction "VSS_1") (pintype "power_in"))
      (node (ref "IC35") (pin "11") (pinfunction "GND_11") (pintype "power_in"))
      (node (ref "IC35") (pin "2") (pinfunction "GND_2") (pintype "power_in"))
      (node (ref "IC35") (pin "5") (pinfunction "GND_5") (pintype "power_in"))
      (node (ref "IC35") (pin "8") (pinfunction "GND_8") (pintype "power_in"))
      (node (ref "J1") (pin "10") (pinfunction "10_10") (pintype "bidirectional"))
      (node (ref "J1") (pin "11") (pinfunction "11_11") (pintype "bidirectional"))
      (node (ref "J1") (pin "15") (pinfunction "15_15") (pintype "bidirectional"))
      (node (ref "J1") (pin "2") (pinfunction "2_2") (pintype "bidirectional"))
      (node (ref "J1") (pin "4") (pinfunction "4_4") (pintype "bidirectional"))
      (node (ref "J1") (pin "6") (pinfunction "6_6") (pintype "bidirectional"))
      (node (ref "J1") (pin "8") (pinfunction "8_8") (pintype "bidirectional"))
      (node (ref "J2") (pin "2") (pinfunction "2_2") (pintype "bidirectional"))
      (node (ref "J3") (pin "2") (pinfunction "2_2") (pintype "bidirectional"))
      (node (ref "J4") (pin "2") (pinfunction "2_2") (pintype "bidirectional"))
      (node (ref "J5") (pin "2") (pinfunction "2_2") (pintype "bidirectional"))
      (node (ref "LD1") (pin "1") (pinfunction "C_1") (pintype "passive"))
      (node (ref "LD1") (pin "3") (pinfunction "C_3") (pintype "passive"))
      (node (ref "LD3") (pin "1") (pinfunction "C_1") (pintype "passive"))
      (node (ref "LD3") (pin "3") (pinfunction "C_3") (pintype "passive"))
      (node (ref "R58") (pin "1") (pinfunction "1_1") (pintype "passive"))
      (node (ref "R63") (pin "1") (pinfunction "1_1") (pintype "passive"))
      (node (ref "R69") (pin "1") (pinfunction "1_1") (pintype "passive"))
      (node (ref "R75") (pin "1") (pinfunction "1_1") (pintype "passive"))
      (node (ref "R80") (pin "1") (pinfunction "1_1") (pintype "passive"))
      (node (ref "R93") (pin "2") (pinfunction "2_2") (pintype "passive"))
      (node (ref "R94") (pin "2") (pinfunction "2_2") (pintype "passive"))
      (node (ref "R95") (pin "2") (pinfunction "2_2") (pintype "passive"))
      (node (ref "R96") (pin "2") (pinfunction "2_2") (pintype "passive"))
      (node (ref "R97") (pin "1") (pinfunction "1_1") (pintype "passive"))
      (node (ref "T3") (pin "2") (pinfunction "S_2") (pintype "passive"))
      (node (ref "T4") (pin "2") (pinfunction "S_2") (pintype "passive"))
      (node (ref "T5") (pin "2") (pinfunction "S_2") (pintype "passive"))
      (node (ref "T6") (pin "2") (pinfunction "S_2") (pintype "passive"))
      (node (ref "T7") (pin "2") (pinfunction "S_2") (pintype "passive"))
      (node (ref "T8") (pin "2") (pinfunction "S_2") (pintype "passive"))
      (node (ref "T9") (pin "2") (pinfunction "S_2") (pintype "passive"))
    )
    (net (code "36") (name "GND_ISO4") (class "Default")
      (node (ref "C1") (pin "1") (pinfunction "1_1") (pintype "passive"))
      (node (ref "C2") (pin "1") (pinfunction "1_1") (pintype "passive"))
      (node (ref "C3") (pin "1") (pinfunction "1_1") (pintype "passive"))
      (node (ref "C96") (pin "1") (pinfunction "1_1") (pintype "passive"))
      (node (ref "C97") (pin "1") (pinfunction "1_1") (pintype "passive"))
      (node (ref "C98") (pin "1") (pinfunction "1_1") (pintype "passive"))
      (node (ref "C99") (pin "1") (pinfunction "1_1") (pintype "passive"))
      (node (ref "D13") (pin "1") (pinfunction "GND_1") (pintype "power_in"))
      (node (ref "D14") (pin "1") (pinfunction "GND_1") (pintype "power_in"))
      (node (ref "IC44") (pin "1") (pinfunction "VSS_1") (pintype "power_in"))
      (node (ref "IC48") (pin "11") (pinfunction "GND_11") (pintype "power_in"))
      (node (ref "IC48") (pin "2") (pinfunction "GND_2") (pintype "power_in"))
      (node (ref "IC48") (pin "5") (pinfunction "GND_5") (pintype "power_in"))
      (node (ref "IC48") (pin "8") (pinfunction "GND_8") (pintype "power_in"))
      (node (ref "J1") (pin "16") (pinfunction "16_16") (pintype "bidirectional"))
      (node (ref "J1") (pin "20") (pinfunction "20_20") (pintype "bidirectional"))
      (node (ref "J1") (pin "22") (pinfunction "22_22") (pintype "bidirectional"))
      (node (ref "J1") (pin "24") (pinfunction "24_24") (pintype "bidirectional"))
      (node (ref "J1") (pin "26") (pinfunction "26_26") (pintype "bidirectional"))
      (node (ref "J1") (pin "28") (pinfunction "28_28") (pintype "bidirectional"))
      (node (ref "J1") (pin "30") (pinfunction "30_30") (pintype "bidirectional"))
      (node (ref "J11") (pin "2") (pinfunction "2_2") (pintype "bidirectional"))
      (node (ref "J12") (pin "2") (pinfunction "2_2") (pintype "bidirectional"))
      (node (ref "J13") (pin "2") (pinfunction "2_2") (pintype "bidirectional"))
      (node (ref "J14") (pin "2") (pinfunction "2_2") (pintype "bidirectional"))
      (node (ref "LD6") (pin "1") (pinfunction "C_1") (pintype "passive"))
      (node (ref "LD6") (pin "3") (pinfunction "C_3") (pintype "passive"))
      (node (ref "LD7") (pin "1") (pinfunction "C_1") (pintype "passive"))
      (node (ref "LD7") (pin "3") (pinfunction "C_3") (pintype "passive"))
      (node (ref "R100") (pin "1") (pinfunction "1_1") (pintype "passive"))
      (node (ref "R104") (pin "1") (pinfunction "1_1") (pintype "passive"))
      (node (ref "R112") (pin "1") (pinfunction "1_1") (pintype "passive"))
      (node (ref "R118") (pin "1") (pinfunction "1_1") (pintype "passive"))
      (node (ref "R124") (pin "1") (pinfunction "1_1") (pintype "passive"))
      (node (ref "R191") (pin "2") (pinfunction "2_2") (pintype "passive"))
      (node (ref "R192") (pin "2") (pinfunction "2_2") (pintype "passive"))
      (node (ref "R195") (pin "2") (pinfunction "2_2") (pintype "passive"))
      (node (ref "R196") (pin "2") (pinfunction "2_2") (pintype "passive"))
      (node (ref "R198") (pin "1") (pinfunction "1_1") (pintype "passive"))
      (node (ref "T10") (pin "2") (pinfunction "S_2") (pintype "passive"))
      (node (ref "T11") (pin "2") (pinfunction "S_2") (pintype "passive"))
      (node (ref "T12") (pin "2") (pinfunction "S_2") (pintype "passive"))
      (node (ref "T13") (pin "2") (pinfunction "S_2") (pintype "passive"))
      (node (ref "T14") (pin "2") (pinfunction "S_2") (pintype "passive"))
      (node (ref "T15") (pin "2") (pinfunction "S_2") (pintype "passive"))
      (node (ref "T16") (pin "2") (pinfunction "S_2") (pintype "passive"))
    )
    (net (code "37") (name "Net-(IC30-RST)") (class "Default")
      (node (ref "IC30") (pin "2") (pinfunction "RST_2") (pintype "output"))
      (node (ref "IC35") (pin "13") (pinfunction "OE_13") (pintype "input"))
      (node (ref "R58") (pin "2") (pinfunction "2_2") (pintype "passive"))
    )
    (net (code "38") (name "Net-(IC35-A1)") (class "Default")
      (node (ref "IC35") (pin "1") (pinfunction "A1_1") (pintype "bidirectional"))
      (node (ref "IC35") (pin "3") (pinfunction "A2_3") (pintype "bidirectional"))
      (node (ref "R78") (pin "2") (pinfunction "2_2") (pintype "passive"))
      (node (ref "R80") (pin "2") (pinfunction "2_2") (pintype "passive"))
    )
    (net (code "39") (name "Net-(IC35-A3)") (class "Default")
      (node (ref "IC35") (pin "4") (pinfunction "A3_4") (pintype "bidirectional"))
      (node (ref "IC35") (pin "6") (pinfunction "A4_6") (pintype "bidirectional"))
      (node (ref "R72") (pin "2") (pinfunction "2_2") (pintype "passive"))
      (node (ref "R75") (pin "2") (pinfunction "2_2") (pintype "passive"))
    )
    (net (code "40") (name "Net-(IC35-A5)") (class "Default")
      (node (ref "IC35") (pin "7") (pinfunction "A5_7") (pintype "bidirectional"))
      (node (ref "IC35") (pin "9") (pinfunction "A6_9") (pintype "bidirectional"))
      (node (ref "R65") (pin "2") (pinfunction "2_2") (pintype "passive"))
      (node (ref "R69") (pin "2") (pinfunction "2_2") (pintype "passive"))
    )
    (net (code "41") (name "Net-(IC35-A7)") (class "Default")
      (node (ref "IC35") (pin "10") (pinfunction "A7_10") (pintype "bidirectional"))
      (node (ref "IC35") (pin "12") (pinfunction "A8_12") (pintype "bidirectional"))
      (node (ref "R60") (pin "2") (pinfunction "2_2") (pintype "passive"))
      (node (ref "R63") (pin "2") (pinfunction "2_2") (pintype "passive"))
    )
    (net (code "42") (name "Net-(IC35-DIR)") (class "Default")
      (node (ref "IC35") (pin "24") (pinfunction "DIR_24") (pintype "input"))
      (node (ref "R90") (pin "1") (pinfunction "1_1") (pintype "passive"))
      (node (ref "T7") (pin "1") (pinfunction "G_1") (pintype "passive"))
      (node (ref "T8") (pin "3") (pinfunction "D_3") (pintype "passive"))
    )
    (net (code "43") (name "Net-(IC44-RST)") (class "Default")
      (node (ref "IC44") (pin "2") (pinfunction "RST_2") (pintype "output"))
      (node (ref "IC48") (pin "13") (pinfunction "OE_13") (pintype "input"))
      (node (ref "R100") (pin "2") (pinfunction "2_2") (pintype "passive"))
    )
    (net (code "44") (name "Net-(IC48-A1)") (class "Default")
      (node (ref "IC48") (pin "1") (pinfunction "A1_1") (pintype "bidirectional"))
      (node (ref "IC48") (pin "3") (pinfunction "A2_3") (pintype "bidirectional"))
      (node (ref "R122") (pin "2") (pinfunction "2_2") (pintype "passive"))
      (node (ref "R124") (pin "2") (pinfunction "2_2") (pintype "passive"))
    )
    (net (code "45") (name "Net-(IC48-A3)") (class "Default")
      (node (ref "IC48") (pin "4") (pinfunction "A3_4") (pintype "bidirectional"))
      (node (ref "IC48") (pin "6") (pinfunction "A4_6") (pintype "bidirectional"))
      (node (ref "R115") (pin "2") (pinfunction "2_2") (pintype "passive"))
      (node (ref "R118") (pin "2") (pinfunction "2_2") (pintype "passive"))
    )
    (net (code "46") (name "Net-(IC48-A5)") (class "Default")
      (node (ref "IC48") (pin "7") (pinfunction "A5_7") (pintype "bidirectional"))
      (node (ref "IC48") (pin "9") (pinfunction "A6_9") (pintype "bidirectional"))
      (node (ref "R107") (pin "2") (pinfunction "2_2") (pintype "passive"))
      (node (ref "R112") (pin "2") (pinfunction "2_2") (pintype "passive"))
    )
    (net (code "47") (name "Net-(IC48-A7)") (class "Default")
      (node (ref "IC48") (pin "10") (pinfunction "A7_10") (pintype "bidirectional"))
      (node (ref "IC48") (pin "12") (pinfunction "A8_12") (pintype "bidirectional"))
      (node (ref "R102") (pin "2") (pinfunction "2_2") (pintype "passive"))
      (node (ref "R104") (pin "2") (pinfunction "2_2") (pintype "passive"))
    )
    (net (code "48") (name "Net-(IC48-DIR)") (class "Default")
      (node (ref "IC48") (pin "24") (pinfunction "DIR_24") (pintype "input"))
      (node (ref "R189") (pin "1") (pinfunction "1_1") (pintype "passive"))
      (node (ref "T14") (pin "1") (pinfunction "G_1") (pintype "passive"))
      (node (ref "T15") (pin "3") (pinfunction "D_3") (pintype "passive"))
    )
    (net (code "49") (name "Net-(LD2A-C)") (class "Default")
      (node (ref "LD2") (pin "1") (pinfunction "C_1") (pintype "passive"))
      (node (ref "R87") (pin "2") (pinfunction "2_2") (pintype "passive"))
    )
    (net (code "50") (name "Net-(LD2B-C)") (class "Default")
      (node (ref "LD2") (pin "3") (pinfunction "C_3") (pintype "passive"))
      (node (ref "R88") (pin "2") (pinfunction "2_2") (pintype "passive"))
    )
    (net (code "51") (name "Net-(LD8A-C)") (class "Default")
      (node (ref "LD8") (pin "1") (pinfunction "C_1") (pintype "passive"))
      (node (ref "R183") (pin "2") (pinfunction "2_2") (pintype "passive"))
    )
    (net (code "52") (name "Net-(LD8B-C)") (class "Default")
      (node (ref "LD8") (pin "3") (pinfunction "C_3") (pintype "passive"))
      (node (ref "R184") (pin "2") (pinfunction "2_2") (pintype "passive"))
    )
    (net (code "53") (name "Net-(T3-D)") (class "Default")
      (node (ref "R62") (pin "1") (pinfunction "1_1") (pintype "passive"))
      (node (ref "T3") (pin "3") (pinfunction "D_3") (pintype "passive"))
    )
    (net (code "54") (name "Net-(T4-D)") (class "Default")
      (node (ref "R68") (pin "1") (pinfunction "1_1") (pintype "passive"))
      (node (ref "T4") (pin "3") (pinfunction "D_3") (pintype "passive"))
    )
    (net (code "55") (name "Net-(T5-D)") (class "Default")
      (node (ref "R74") (pin "1") (pinfunction "1_1") (pintype "passive"))
      (node (ref "T5") (pin "3") (pinfunction "D_3") (pintype "passive"))
    )
    (net (code "56") (name "Net-(T6-D)") (class "Default")
      (node (ref "R79") (pin "1") (pinfunction "1_1") (pintype "passive"))
      (node (ref "T6") (pin "3") (pinfunction "D_3") (pintype "passive"))
    )
    (net (code "57") (name "Net-(T7-D)") (class "Default")
      (node (ref "R88") (pin "1") (pinfunction "1_1") (pintype "passive"))
      (node (ref "T7") (pin "3") (pinfunction "D_3") (pintype "passive"))
    )
    (net (code "58") (name "Net-(T9-D)") (class "Default")
      (node (ref "R87") (pin "1") (pinfunction "1_1") (pintype "passive"))
      (node (ref "T9") (pin "3") (pinfunction "D_3") (pintype "passive"))
    )
    (net (code "59") (name "Net-(T10-D)") (class "Default")
      (node (ref "R105") (pin "1") (pinfunction "1_1") (pintype "passive"))
      (node (ref "T10") (pin "3") (pinfunction "D_3") (pintype "passive"))
    )
    (net (code "60") (name "Net-(T11-D)") (class "Default")
      (node (ref "R111") (pin "1") (pinfunction "1_1") (pintype "passive"))
      (node (ref "T11") (pin "3") (pinfunction "D_3") (pintype "passive"))
    )
    (net (code "61") (name "Net-(T12-D)") (class "Default")
      (node (ref "R117") (pin "1") (pinfunction "1_1") (pintype "passive"))
      (node (ref "T12") (pin "3") (pinfunction "D_3") (pintype "passive"))
    )
    (net (code "62") (name "Net-(T13-D)") (class "Default")
      (node (ref "R123") (pin "1") (pinfunction "1_1") (pintype "passive"))
      (node (ref "T13") (pin "3") (pinfunction "D_3") (pintype "passive"))
    )
    (net (code "63") (name "Net-(T14-D)") (class "Default")
      (node (ref "R184") (pin "1") (pinfunction "1_1") (pintype "passive"))
      (node (ref "T14") (pin "3") (pinfunction "D_3") (pintype "passive"))
    )
    (net (code "64") (name "Net-(T16-D)") (class "Default")
      (node (ref "R183") (pin "1") (pinfunction "1_1") (pintype "passive"))
      (node (ref "T16") (pin "3") (pinfunction "D_3") (pintype "passive"))
    )
    (net (code "65") (name "P5V0_ISO3") (class "Default")
      (node (ref "C4") (pin "2") (pinfunction "2_2") (pintype "passive"))
      (node (ref "C5") (pin "2") (pinfunction "2_2") (pintype "passive"))
      (node (ref "C6") (pin "2") (pinfunction "2_2") (pintype "passive"))
      (node (ref "D4") (pin "4") (pinfunction "VCC_4") (pintype "power_in"))
      (node (ref "D9") (pin "4") (pinfunction "VCC_4") (pintype "power_in"))
      (node (ref "IC30") (pin "3") (pinfunction "VDD_3") (pintype "power_in"))
      (node (ref "IC35") (pin "16") (pinfunction "VCC_16") (pintype "power_in"))
      (node (ref "IC35") (pin "21") (pinfunction "VCC_21") (pintype "power_in"))
      (node (ref "J1") (pin "12") (pinfunction "12_12") (pintype "bidirectional"))
      (node (ref "J1") (pin "13") (pinfunction "13_13") (pintype "bidirectional"))
      (node (ref "J1") (pin "14") (pinfunction "14_14") (pintype "bidirectional"))
      (node (ref "LD2") (pin "2") (pinfunction "A_2") (pintype "passive"))
      (node (ref "LD2") (pin "4") (pinfunction "A_4") (pintype "passive"))
      (node (ref "R90") (pin "2") (pinfunction "2_2") (pintype "passive"))
      (node (ref "SW2") (pin "1") (pinfunction "1_1") (pintype "passive"))
      (node (ref "SW2") (pin "2") (pinfunction "2_2") (pintype "passive"))
      (node (ref "SW2") (pin "3") (pinfunction "3_3") (pintype "passive"))
      (node (ref "SW2") (pin "4") (pinfunction "4_4") (pintype "passive"))
    )
    (net (code "66") (name "P5V0_ISO4") (class "Default")
      (node (ref "C1") (pin "2") (pinfunction "2_2") (pintype "passive"))
      (node (ref "C2") (pin "2") (pinfunction "2_2") (pintype "passive"))
      (node (ref "C3") (pin "2") (pinfunction "2_2") (pintype "passive"))
      (node (ref "D13") (pin "4") (pinfunction "VCC_4") (pintype "power_in"))
      (node (ref "D14") (pin "4") (pinfunction "VCC_4") (pintype "power_in"))
      (node (ref "IC44") (pin "3") (pinfunction "VDD_3") (pintype "power_in"))
      (node (ref "IC48") (pin "16") (pinfunction "VCC_16") (pintype "power_in"))
      (node (ref "IC48") (pin "21") (pinfunction "VCC_21") (pintype "power_in"))
      (node (ref "J1") (pin "17") (pinfunction "17_17") (pintype "bidirectional"))
      (node (ref "J1") (pin "18") (pinfunction "18_18") (pintype "bidirectional"))
      (node (ref "J1") (pin "19") (pinfunction "19_19") (pintype "bidirectional"))
      (node (ref "LD8") (pin "2") (pinfunction "A_2") (pintype "passive"))
      (node (ref "LD8") (pin "4") (pinfunction "A_4") (pintype "passive"))
      (node (ref "R189") (pin "2") (pinfunction "2_2") (pintype "passive"))
      (node (ref "SW4") (pin "1") (pinfunction "1_1") (pintype "passive"))
      (node (ref "SW4") (pin "2") (pinfunction "2_2") (pintype "passive"))
      (node (ref "SW4") (pin "3") (pinfunction "3_3") (pintype "passive"))
      (node (ref "SW4") (pin "4") (pinfunction "4_4") (pintype "passive"))
    )
    (net (code "67") (name "unconnected-(M1-Pad1)") (class "Default")
      (node (ref "M1") (pin "1") (pinfunction "1_1") (pintype "bidirectional+no_connect"))
    )
    (net (code "68") (name "unconnected-(M2-Pad1)") (class "Default")
      (node (ref "M2") (pin "1") (pinfunction "1_1") (pintype "bidirectional+no_connect"))
    )
  )
)
